# Sheet1.net
KiCad netlist of a schematic drawn in Altium Designer
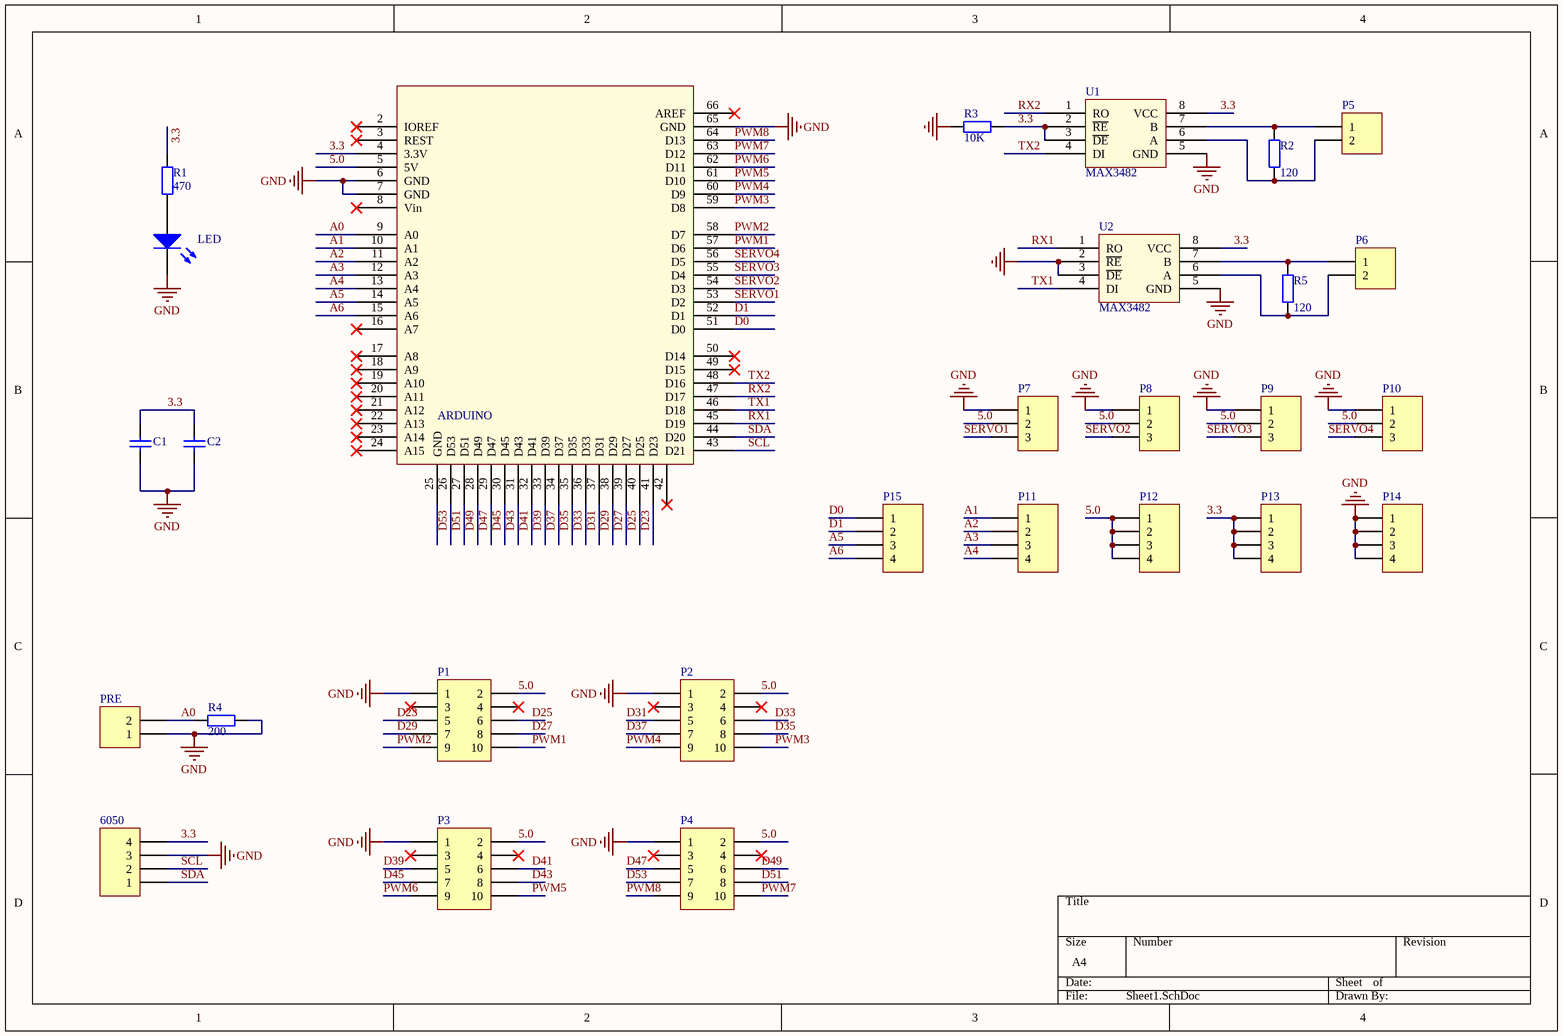
[diagram p0: Sheet1.SchDoc]

(export (version "E")
  (design (tool "Eeschema 10.0.6"))
  (components
    (comp (ref "6050")
      (value "Header 4")
      (footprint "HDR1X4")
      (description "Header, 4-Pin")
      (fields (field (name "PUBLISHER") "Altium Limited"))
      (libsource (lib "Miscellaneous Connectors") (part "Header 4"))
    )
    (comp (ref "ARDUINO")
      (value "2560")
      (footprint "ARDUINO")
      (libsource (lib "Schlib1") (part "Component_1"))
    )
    (comp (ref "C1")
      (value "Cap")
      (footprint "0805")
      (description "Capacitor")
      (fields (field (name "PUBLISHER") "Altium Limited"))
      (libsource (lib "Miscellaneous Devices") (part "Cap"))
    )
    (comp (ref "C2")
      (value "Cap")
      (footprint "0805")
      (description "Capacitor")
      (fields (field (name "PUBLISHER") "Altium Limited"))
      (libsource (lib "Miscellaneous Devices") (part "Cap"))
    )
    (comp (ref "LED")
      (value "LED0")
      (footprint "0805")
      (description "Typical INFRARED GaAs LED")
      (fields (field (name "PUBLISHER") "Altium Limited"))
      (libsource (lib "Miscellaneous Devices") (part "LED0"))
    )
    (comp (ref "P1")
      (value "Header 5X2")
      (footprint "HDR2X5")
      (description "Header, 5-Pin, Dual row")
      (fields (field (name "PUBLISHER") "Altium Limited"))
      (libsource (lib "Miscellaneous Connectors") (part "Header 5X2"))
    )
    (comp (ref "P2")
      (value "Header 5X2")
      (footprint "HDR2X5")
      (description "Header, 5-Pin, Dual row")
      (fields (field (name "PUBLISHER") "Altium Limited"))
      (libsource (lib "Miscellaneous Connectors") (part "Header 5X2"))
    )
    (comp (ref "P3")
      (value "Header 5X2")
      (footprint "HDR2X5")
      (description "Header, 5-Pin, Dual row")
      (fields (field (name "PUBLISHER") "Altium Limited"))
      (libsource (lib "Miscellaneous Connectors") (part "Header 5X2"))
    )
    (comp (ref "P4")
      (value "Header 5X2")
      (footprint "HDR2X5")
      (description "Header, 5-Pin, Dual row")
      (fields (field (name "PUBLISHER") "Altium Limited"))
      (libsource (lib "Miscellaneous Connectors") (part "Header 5X2"))
    )
    (comp (ref "P5")
      (value "Header 2")
      (footprint "蓝色电源插座")
      (description "Header, 2-Pin")
      (fields (field (name "PUBLISHER") "Altium Limited"))
      (libsource (lib "") (part "Header 2_1"))
    )
    (comp (ref "P6")
      (value "Header 2")
      (footprint "蓝色电源插座")
      (description "Header, 2-Pin")
      (fields (field (name "PUBLISHER") "Altium Limited"))
      (libsource (lib "") (part "Header 2_1"))
    )
    (comp (ref "P7")
      (value "Header 3")
      (footprint "HDR1X3")
      (description "Header, 3-Pin")
      (fields (field (name "PUBLISHER") "Altium Limited"))
      (libsource (lib "Miscellaneous Connectors") (part "Header 3"))
    )
    (comp (ref "P8")
      (value "Header 3")
      (footprint "HDR1X3")
      (description "Header, 3-Pin")
      (fields (field (name "PUBLISHER") "Altium Limited"))
      (libsource (lib "Miscellaneous Connectors") (part "Header 3"))
    )
    (comp (ref "P9")
      (value "Header 3")
      (footprint "HDR1X3")
      (description "Header, 3-Pin")
      (fields (field (name "PUBLISHER") "Altium Limited"))
      (libsource (lib "Miscellaneous Connectors") (part "Header 3"))
    )
    (comp (ref "P10")
      (value "Header 3")
      (footprint "HDR1X3")
      (description "Header, 3-Pin")
      (fields (field (name "PUBLISHER") "Altium Limited"))
      (libsource (lib "Miscellaneous Connectors") (part "Header 3"))
    )
    (comp (ref "P11")
      (value "Header 4")
      (footprint "HDR1X4")
      (description "Header, 4-Pin")
      (fields (field (name "PUBLISHER") "Altium Limited"))
      (libsource (lib "") (part "Header 4_1"))
    )
    (comp (ref "P12")
      (value "Header 4")
      (footprint "HDR1X4")
      (description "Header, 4-Pin")
      (fields (field (name "PUBLISHER") "Altium Limited"))
      (libsource (lib "") (part "Header 4_1"))
    )
    (comp (ref "P13")
      (value "Header 4")
      (footprint "HDR1X4")
      (description "Header, 4-Pin")
      (fields (field (name "PUBLISHER") "Altium Limited"))
      (libsource (lib "") (part "Header 4_1"))
    )
    (comp (ref "P14")
      (value "Header 4")
      (footprint "HDR1X4")
      (description "Header, 4-Pin")
      (fields (field (name "PUBLISHER") "Altium Limited"))
      (libsource (lib "") (part "Header 4_1"))
    )
    (comp (ref "P15")
      (value "Header 4")
      (footprint "HDR1X4")
      (description "Header, 4-Pin")
      (fields (field (name "PUBLISHER") "Altium Limited"))
      (libsource (lib "") (part "Header 4_1"))
    )
    (comp (ref "PRE")
      (value "Header 2")
      (footprint "HDR1X2")
      (description "Header, 2-Pin")
      (fields (field (name "PUBLISHER") "Altium Limited"))
      (libsource (lib "Miscellaneous Connectors") (part "Header 2"))
    )
    (comp (ref "R1")
      (value "470")
      (footprint "0805")
      (description "Resistor")
      (fields (field (name "Comment") "Res2") (field (name "PUBLISHER") "Altium Limited"))
      (libsource (lib "") (part "Res2_3"))
    )
    (comp (ref "R2")
      (value "120")
      (footprint "0805")
      (description "Resistor")
      (fields (field (name "Comment") "Res2") (field (name "PUBLISHER") "Altium Limited"))
      (libsource (lib "Miscellaneous Devices") (part "Res2"))
    )
    (comp (ref "R3")
      (value "10K")
      (footprint "0805")
      (description "Resistor")
      (fields (field (name "Comment") "Res2") (field (name "PUBLISHER") "Altium Limited"))
      (libsource (lib "") (part "Res2_1"))
    )
    (comp (ref "R4")
      (value "200")
      (footprint "0805")
      (description "Resistor")
      (fields (field (name "Comment") "Res2") (field (name "PUBLISHER") "Altium Limited"))
      (libsource (lib "") (part "Res2_2"))
    )
    (comp (ref "R5")
      (value "120")
      (footprint "0805")
      (description "Resistor")
      (fields (field (name "Comment") "Res2") (field (name "PUBLISHER") "Altium Limited"))
      (libsource (lib "Miscellaneous Devices") (part "Res2"))
    )
    (comp (ref "U1") (value "MAX3482") (footprint "3485") (libsource (lib "Schlib1") (part "MAX3482")))
    (comp (ref "U2") (value "MAX3482") (footprint "3485") (libsource (lib "Schlib1") (part "MAX3482")))
  )
  (nets
    (net (code "1") (name "/3.3") (class "Default")
      (node (ref "6050") (pin "4") (pinfunction "4_4") (pintype "passive"))
      (node (ref "ARDUINO") (pin "4") (pinfunction "3.3V_4") (pintype "passive"))
      (node (ref "C1") (pin "2") (pinfunction "2_2") (pintype "passive"))
      (node (ref "C2") (pin "2") (pinfunction "2_2") (pintype "passive"))
      (node (ref "P13") (pin "1") (pinfunction "1_1") (pintype "passive"))
      (node (ref "P13") (pin "2") (pinfunction "2_2") (pintype "passive"))
      (node (ref "P13") (pin "3") (pinfunction "3_3") (pintype "passive"))
      (node (ref "P13") (pin "4") (pinfunction "4_4") (pintype "passive"))
      (node (ref "R1") (pin "1") (pinfunction "1_1") (pintype "passive"))
      (node (ref "R3") (pin "1") (pinfunction "1_1") (pintype "passive"))
      (node (ref "U1") (pin "2") (pinfunction "~{RE}_2") (pintype "passive"))
      (node (ref "U1") (pin "3") (pinfunction "~{DE}_3") (pintype "passive"))
      (node (ref "U1") (pin "8") (pinfunction "VCC_8") (pintype "passive"))
      (node (ref "U2") (pin "8") (pinfunction "VCC_8") (pintype "passive"))
    )
    (net (code "2") (name "/5.0") (class "Default")
      (node (ref "ARDUINO") (pin "5") (pinfunction "5V_5") (pintype "passive"))
      (node (ref "P1") (pin "2") (pinfunction "2_2") (pintype "passive"))
      (node (ref "P10") (pin "2") (pinfunction "2_2") (pintype "passive"))
      (node (ref "P12") (pin "1") (pinfunction "1_1") (pintype "passive"))
      (node (ref "P12") (pin "2") (pinfunction "2_2") (pintype "passive"))
      (node (ref "P12") (pin "3") (pinfunction "3_3") (pintype "passive"))
      (node (ref "P12") (pin "4") (pinfunction "4_4") (pintype "passive"))
      (node (ref "P2") (pin "2") (pinfunction "2_2") (pintype "passive"))
      (node (ref "P3") (pin "2") (pinfunction "2_2") (pintype "passive"))
      (node (ref "P4") (pin "2") (pinfunction "2_2") (pintype "passive"))
      (node (ref "P7") (pin "2") (pinfunction "2_2") (pintype "passive"))
      (node (ref "P8") (pin "2") (pinfunction "2_2") (pintype "passive"))
      (node (ref "P9") (pin "2") (pinfunction "2_2") (pintype "passive"))
    )
    (net (code "3") (name "/A0") (class "Default")
      (node (ref "ARDUINO") (pin "9") (pinfunction "A0_9") (pintype "passive"))
      (node (ref "PRE") (pin "2") (pinfunction "2_2") (pintype "passive"))
      (node (ref "R4") (pin "1") (pinfunction "1_1") (pintype "passive"))
    )
    (net (code "4") (name "/A1") (class "Default")
      (node (ref "ARDUINO") (pin "10") (pinfunction "A1_10") (pintype "passive"))
      (node (ref "P11") (pin "1") (pinfunction "1_1") (pintype "passive"))
    )
    (net (code "5") (name "/A2") (class "Default")
      (node (ref "ARDUINO") (pin "11") (pinfunction "A2_11") (pintype "passive"))
      (node (ref "P11") (pin "2") (pinfunction "2_2") (pintype "passive"))
    )
    (net (code "6") (name "/A3") (class "Default")
      (node (ref "ARDUINO") (pin "12") (pinfunction "A3_12") (pintype "passive"))
      (node (ref "P11") (pin "3") (pinfunction "3_3") (pintype "passive"))
    )
    (net (code "7") (name "/A4") (class "Default")
      (node (ref "ARDUINO") (pin "13") (pinfunction "A4_13") (pintype "passive"))
      (node (ref "P11") (pin "4") (pinfunction "4_4") (pintype "passive"))
    )
    (net (code "8") (name "/A5") (class "Default")
      (node (ref "ARDUINO") (pin "14") (pinfunction "A5_14") (pintype "passive"))
      (node (ref "P15") (pin "3") (pinfunction "3_3") (pintype "passive"))
    )
    (net (code "9") (name "/A6") (class "Default")
      (node (ref "ARDUINO") (pin "15") (pinfunction "A6_15") (pintype "passive"))
      (node (ref "P15") (pin "4") (pinfunction "4_4") (pintype "passive"))
    )
    (net (code "10") (name "/D0") (class "Default")
      (node (ref "ARDUINO") (pin "51") (pinfunction "D0_51") (pintype "passive"))
      (node (ref "P15") (pin "1") (pinfunction "1_1") (pintype "passive"))
    )
    (net (code "11") (name "/D1") (class "Default")
      (node (ref "ARDUINO") (pin "52") (pinfunction "D1_52") (pintype "passive"))
      (node (ref "P15") (pin "2") (pinfunction "2_2") (pintype "passive"))
    )
    (net (code "12") (name "/D23") (class "Default")
      (node (ref "ARDUINO") (pin "41") (pinfunction "D23_41") (pintype "passive"))
      (node (ref "P1") (pin "5") (pinfunction "5_5") (pintype "passive"))
    )
    (net (code "13") (name "/D25") (class "Default")
      (node (ref "ARDUINO") (pin "40") (pinfunction "D25_40") (pintype "passive"))
      (node (ref "P1") (pin "6") (pinfunction "6_6") (pintype "passive"))
    )
    (net (code "14") (name "/D27") (class "Default")
      (node (ref "ARDUINO") (pin "39") (pinfunction "D27_39") (pintype "passive"))
      (node (ref "P1") (pin "8") (pinfunction "8_8") (pintype "passive"))
    )
    (net (code "15") (name "/D29") (class "Default")
      (node (ref "ARDUINO") (pin "38") (pinfunction "D29_38") (pintype "passive"))
      (node (ref "P1") (pin "7") (pinfunction "7_7") (pintype "passive"))
    )
    (net (code "16") (name "/D31") (class "Default")
      (node (ref "ARDUINO") (pin "37") (pinfunction "D31_37") (pintype "passive"))
      (node (ref "P2") (pin "5") (pinfunction "5_5") (pintype "passive"))
    )
    (net (code "17") (name "/D33") (class "Default")
      (node (ref "ARDUINO") (pin "36") (pinfunction "D33_36") (pintype "passive"))
      (node (ref "P2") (pin "6") (pinfunction "6_6") (pintype "passive"))
    )
    (net (code "18") (name "/D35") (class "Default")
      (node (ref "ARDUINO") (pin "35") (pinfunction "D35_35") (pintype "passive"))
      (node (ref "P2") (pin "8") (pinfunction "8_8") (pintype "passive"))
    )
    (net (code "19") (name "/D37") (class "Default")
      (node (ref "ARDUINO") (pin "34") (pinfunction "D37_34") (pintype "passive"))
      (node (ref "P2") (pin "7") (pinfunction "7_7") (pintype "passive"))
    )
    (net (code "20") (name "/D39") (class "Default")
      (node (ref "ARDUINO") (pin "33") (pinfunction "D39_33") (pintype "passive"))
      (node (ref "P3") (pin "5") (pinfunction "5_5") (pintype "passive"))
    )
    (net (code "21") (name "/D41") (class "Default")
      (node (ref "ARDUINO") (pin "32") (pinfunction "D41_32") (pintype "passive"))
      (node (ref "P3") (pin "6") (pinfunction "6_6") (pintype "passive"))
    )
    (net (code "22") (name "/D43") (class "Default")
      (node (ref "ARDUINO") (pin "31") (pinfunction "D43_31") (pintype "passive"))
      (node (ref "P3") (pin "8") (pinfunction "8_8") (pintype "passive"))
    )
    (net (code "23") (name "/D45") (class "Default")
      (node (ref "ARDUINO") (pin "30") (pinfunction "D45_30") (pintype "passive"))
      (node (ref "P3") (pin "7") (pinfunction "7_7") (pintype "passive"))
    )
    (net (code "24") (name "/D47") (class "Default")
      (node (ref "ARDUINO") (pin "29") (pinfunction "D47_29") (pintype "passive"))
      (node (ref "P4") (pin "5") (pinfunction "5_5") (pintype "passive"))
    )
    (net (code "25") (name "/D49") (class "Default")
      (node (ref "ARDUINO") (pin "28") (pinfunction "D49_28") (pintype "passive"))
      (node (ref "P4") (pin "6") (pinfunction "6_6") (pintype "passive"))
    )
    (net (code "26") (name "/D51") (class "Default")
      (node (ref "ARDUINO") (pin "27") (pinfunction "D51_27") (pintype "passive"))
      (node (ref "P4") (pin "8") (pinfunction "8_8") (pintype "passive"))
    )
    (net (code "27") (name "/D53") (class "Default")
      (node (ref "ARDUINO") (pin "26") (pinfunction "D53_26") (pintype "passive"))
      (node (ref "P4") (pin "7") (pinfunction "7_7") (pintype "passive"))
    )
    (net (code "28") (name "/PWM1") (class "Default")
      (node (ref "ARDUINO") (pin "57") (pinfunction "D6_57") (pintype "passive"))
      (node (ref "P1") (pin "10") (pinfunction "10_10") (pintype "passive"))
    )
    (net (code "29") (name "/PWM2") (class "Default")
      (node (ref "ARDUINO") (pin "58") (pinfunction "D7_58") (pintype "passive"))
      (node (ref "P1") (pin "9") (pinfunction "9_9") (pintype "passive"))
    )
    (net (code "30") (name "/PWM3") (class "Default")
      (node (ref "ARDUINO") (pin "59") (pinfunction "D8_59") (pintype "passive"))
      (node (ref "P2") (pin "10") (pinfunction "10_10") (pintype "passive"))
    )
    (net (code "31") (name "/PWM4") (class "Default")
      (node (ref "ARDUINO") (pin "60") (pinfunction "D9_60") (pintype "passive"))
      (node (ref "P2") (pin "9") (pinfunction "9_9") (pintype "passive"))
    )
    (net (code "32") (name "/PWM5") (class "Default")
      (node (ref "ARDUINO") (pin "61") (pinfunction "D10_61") (pintype "passive"))
      (node (ref "P3") (pin "10") (pinfunction "10_10") (pintype "passive"))
    )
    (net (code "33") (name "/PWM6") (class "Default")
      (node (ref "ARDUINO") (pin "62") (pinfunction "D11_62") (pintype "passive"))
      (node (ref "P3") (pin "9") (pinfunction "9_9") (pintype "passive"))
    )
    (net (code "34") (name "/PWM7") (class "Default")
      (node (ref "ARDUINO") (pin "63") (pinfunction "D12_63") (pintype "passive"))
      (node (ref "P4") (pin "10") (pinfunction "10_10") (pintype "passive"))
    )
    (net (code "35") (name "/PWM8") (class "Default")
      (node (ref "ARDUINO") (pin "64") (pinfunction "D13_64") (pintype "passive"))
      (node (ref "P4") (pin "9") (pinfunction "9_9") (pintype "passive"))
    )
    (net (code "36") (name "/RX1") (class "Default")
      (node (ref "ARDUINO") (pin "45") (pinfunction "D19_45") (pintype "passive"))
      (node (ref "U2") (pin "1") (pinfunction "RO_1") (pintype "passive"))
    )
    (net (code "37") (name "/RX2") (class "Default")
      (node (ref "ARDUINO") (pin "47") (pinfunction "D17_47") (pintype "passive"))
      (node (ref "U1") (pin "1") (pinfunction "RO_1") (pintype "passive"))
    )
    (net (code "38") (name "/SCL") (class "Default")
      (node (ref "6050") (pin "2") (pinfunction "2_2") (pintype "passive"))
      (node (ref "ARDUINO") (pin "43") (pinfunction "D21_43") (pintype "passive"))
    )
    (net (code "39") (name "/SDA") (class "Default")
      (node (ref "6050") (pin "1") (pinfunction "1_1") (pintype "passive"))
      (node (ref "ARDUINO") (pin "44") (pinfunction "D20_44") (pintype "passive"))
    )
    (net (code "40") (name "/SERVO1") (class "Default")
      (node (ref "ARDUINO") (pin "53") (pinfunction "D2_53") (pintype "passive"))
      (node (ref "P7") (pin "3") (pinfunction "3_3") (pintype "passive"))
    )
    (net (code "41") (name "/SERVO2") (class "Default")
      (node (ref "ARDUINO") (pin "54") (pinfunction "D3_54") (pintype "passive"))
      (node (ref "P8") (pin "3") (pinfunction "3_3") (pintype "passive"))
    )
    (net (code "42") (name "/SERVO3") (class "Default")
      (node (ref "ARDUINO") (pin "55") (pinfunction "D4_55") (pintype "passive"))
      (node (ref "P9") (pin "3") (pinfunction "3_3") (pintype "passive"))
    )
    (net (code "43") (name "/SERVO4") (class "Default")
      (node (ref "ARDUINO") (pin "56") (pinfunction "D5_56") (pintype "passive"))
      (node (ref "P10") (pin "3") (pinfunction "3_3") (pintype "passive"))
    )
    (net (code "44") (name "/TX1") (class "Default")
      (node (ref "ARDUINO") (pin "46") (pinfunction "D18_46") (pintype "passive"))
      (node (ref "U2") (pin "4") (pinfunction "DI_4") (pintype "passive"))
    )
    (net (code "45") (name "/TX2") (class "Default")
      (node (ref "ARDUINO") (pin "48") (pinfunction "D16_48") (pintype "passive"))
      (node (ref "U1") (pin "4") (pinfunction "DI_4") (pintype "passive"))
    )
    (net (code "46") (name "GND") (class "Default")
      (node (ref "6050") (pin "3") (pinfunction "3_3") (pintype "passive"))
      (node (ref "ARDUINO") (pin "6") (pinfunction "GND_6") (pintype "passive"))
      (node (ref "ARDUINO") (pin "65") (pinfunction "GND_65") (pintype "passive"))
      (node (ref "ARDUINO") (pin "7") (pinfunction "GND_7") (pintype "passive"))
      (node (ref "C1") (pin "1") (pinfunction "1_1") (pintype "passive"))
      (node (ref "C2") (pin "1") (pinfunction "1_1") (pintype "passive"))
      (node (ref "LED") (pin "2") (pinfunction "K_2") (pintype "passive"))
      (node (ref "P1") (pin "1") (pinfunction "1_1") (pintype "passive"))
      (node (ref "P10") (pin "1") (pinfunction "1_1") (pintype "passive"))
      (node (ref "P14") (pin "1") (pinfunction "1_1") (pintype "passive"))
      (node (ref "P14") (pin "2") (pinfunction "2_2") (pintype "passive"))
      (node (ref "P14") (pin "3") (pinfunction "3_3") (pintype "passive"))
      (node (ref "P14") (pin "4") (pinfunction "4_4") (pintype "passive"))
      (node (ref "P2") (pin "1") (pinfunction "1_1") (pintype "passive"))
      (node (ref "P3") (pin "1") (pinfunction "1_1") (pintype "passive"))
      (node (ref "P4") (pin "1") (pinfunction "1_1") (pintype "passive"))
      (node (ref "P7") (pin "1") (pinfunction "1_1") (pintype "passive"))
      (node (ref "P8") (pin "1") (pinfunction "1_1") (pintype "passive"))
      (node (ref "P9") (pin "1") (pinfunction "1_1") (pintype "passive"))
      (node (ref "PRE") (pin "1") (pinfunction "1_1") (pintype "passive"))
      (node (ref "R3") (pin "2") (pinfunction "2_2") (pintype "passive"))
      (node (ref "R4") (pin "2") (pinfunction "2_2") (pintype "passive"))
      (node (ref "U1") (pin "5") (pinfunction "GND_5") (pintype "passive"))
      (node (ref "U2") (pin "2") (pinfunction "~{RE}_2") (pintype "passive"))
      (node (ref "U2") (pin "3") (pinfunction "~{DE}_3") (pintype "passive"))
      (node (ref "U2") (pin "5") (pinfunction "GND_5") (pintype "passive"))
    )
    (net (code "47") (name "Net-(LED-A)") (class "Default")
      (node (ref "LED") (pin "1") (pinfunction "A_1") (pintype "passive"))
      (node (ref "R1") (pin "2") (pinfunction "2_2") (pintype "passive"))
    )
    (net (code "48") (name "Net-(P5-1)") (class "Default")
      (node (ref "P5") (pin "2") (pinfunction "1_2") (pintype "passive"))
      (node (ref "R2") (pin "2") (pinfunction "2_2") (pintype "passive"))
      (node (ref "U1") (pin "7") (pinfunction "B_7") (pintype "passive"))
    )
    (net (code "49") (name "Net-(P5-2)") (class "Default")
      (node (ref "P5") (pin "1") (pinfunction "2_1") (pintype "passive"))
      (node (ref "R2") (pin "1") (pinfunction "1_1") (pintype "passive"))
      (node (ref "U1") (pin "6") (pinfunction "A_6") (pintype "passive"))
    )
    (net (code "50") (name "Net-(P6-1)") (class "Default")
      (node (ref "P6") (pin "2") (pinfunction "1_2") (pintype "passive"))
      (node (ref "R5") (pin "2") (pinfunction "2_2") (pintype "passive"))
      (node (ref "U2") (pin "7") (pinfunction "B_7") (pintype "passive"))
    )
    (net (code "51") (name "Net-(P6-2)") (class "Default")
      (node (ref "P6") (pin "1") (pinfunction "2_1") (pintype "passive"))
      (node (ref "R5") (pin "1") (pinfunction "1_1") (pintype "passive"))
      (node (ref "U2") (pin "6") (pinfunction "A_6") (pintype "passive"))
    )
    (net (code "52") (name "unconnected-(ARDUINO-A7-Pad16)") (class "Default")
      (node (ref "ARDUINO") (pin "16") (pinfunction "A7_16") (pintype "passive+no_connect"))
    )
    (net (code "53") (name "unconnected-(ARDUINO-A8-Pad17)") (class "Default")
      (node (ref "ARDUINO") (pin "17") (pinfunction "A8_17") (pintype "passive+no_connect"))
    )
    (net (code "54") (name "unconnected-(ARDUINO-A9-Pad18)") (class "Default")
      (node (ref "ARDUINO") (pin "18") (pinfunction "A9_18") (pintype "passive+no_connect"))
    )
    (net (code "55") (name "unconnected-(ARDUINO-A10-Pad19)") (class "Default")
      (node (ref "ARDUINO") (pin "19") (pinfunction "A10_19") (pintype "passive+no_connect"))
    )
    (net (code "56") (name "unconnected-(ARDUINO-A11-Pad20)") (class "Default")
      (node (ref "ARDUINO") (pin "20") (pinfunction "A11_20") (pintype "passive+no_connect"))
    )
    (net (code "57") (name "unconnected-(ARDUINO-A12-Pad21)") (class "Default")
      (node (ref "ARDUINO") (pin "21") (pinfunction "A12_21") (pintype "passive+no_connect"))
    )
    (net (code "58") (name "unconnected-(ARDUINO-A13-Pad22)") (class "Default")
      (node (ref "ARDUINO") (pin "22") (pinfunction "A13_22") (pintype "passive+no_connect"))
    )
    (net (code "59") (name "unconnected-(ARDUINO-A14-Pad23)") (class "Default")
      (node (ref "ARDUINO") (pin "23") (pinfunction "A14_23") (pintype "passive+no_connect"))
    )
    (net (code "60") (name "unconnected-(ARDUINO-A15-Pad24)") (class "Default")
      (node (ref "ARDUINO") (pin "24") (pinfunction "A15_24") (pintype "passive+no_connect"))
    )
    (net (code "61") (name "unconnected-(ARDUINO-AREF-Pad66)") (class "Default")
      (node (ref "ARDUINO") (pin "66") (pinfunction "AREF_66") (pintype "passive+no_connect"))
    )
    (net (code "62") (name "unconnected-(ARDUINO-D14-Pad50)") (class "Default")
      (node (ref "ARDUINO") (pin "50") (pinfunction "D14_50") (pintype "passive+no_connect"))
    )
    (net (code "63") (name "unconnected-(ARDUINO-D15-Pad49)") (class "Default")
      (node (ref "ARDUINO") (pin "49") (pinfunction "D15_49") (pintype "passive+no_connect"))
    )
    (net (code "64") (name "unconnected-(ARDUINO-GND-Pad25)") (class "Default")
      (node (ref "ARDUINO") (pin "25") (pinfunction "GND_25") (pintype "passive"))
    )
    (net (code "65") (name "unconnected-(ARDUINO-IOREF-Pad2)") (class "Default")
      (node (ref "ARDUINO") (pin "2") (pinfunction "IOREF_2") (pintype "passive+no_connect"))
    )
    (net (code "66") (name "unconnected-(ARDUINO-Pad42)") (class "Default")
      (node (ref "ARDUINO") (pin "42") (pintype "passive+no_connect"))
    )
    (net (code "67") (name "unconnected-(ARDUINO-REST-Pad3)") (class "Default")
      (node (ref "ARDUINO") (pin "3") (pinfunction "REST_3") (pintype "passive+no_connect"))
    )
    (net (code "68") (name "unconnected-(ARDUINO-Vin-Pad8)") (class "Default")
      (node (ref "ARDUINO") (pin "8") (pinfunction "Vin_8") (pintype "passive+no_connect"))
    )
    (net (code "69") (name "unconnected-(P1-Pad3)") (class "Default")
      (node (ref "P1") (pin "3") (pinfunction "3_3") (pintype "passive+no_connect"))
    )
    (net (code "70") (name "unconnected-(P1-Pad4)") (class "Default")
      (node (ref "P1") (pin "4") (pinfunction "4_4") (pintype "passive+no_connect"))
    )
    (net (code "71") (name "unconnected-(P2-Pad3)") (class "Default")
      (node (ref "P2") (pin "3") (pinfunction "3_3") (pintype "passive+no_connect"))
    )
    (net (code "72") (name "unconnected-(P2-Pad4)") (class "Default")
      (node (ref "P2") (pin "4") (pinfunction "4_4") (pintype "passive+no_connect"))
    )
    (net (code "73") (name "unconnected-(P3-Pad3)") (class "Default")
      (node (ref "P3") (pin "3") (pinfunction "3_3") (pintype "passive+no_connect"))
    )
    (net (code "74") (name "unconnected-(P3-Pad4)") (class "Default")
      (node (ref "P3") (pin "4") (pinfunction "4_4") (pintype "passive+no_connect"))
    )
    (net (code "75") (name "unconnected-(P4-Pad3)") (class "Default")
      (node (ref "P4") (pin "3") (pinfunction "3_3") (pintype "passive+no_connect"))
    )
    (net (code "76") (name "unconnected-(P4-Pad4)") (class "Default")
      (node (ref "P4") (pin "4") (pinfunction "4_4") (pintype "passive+no_connect"))
    )
  )
)
